# 3_3V-Regulator.net
KiCad netlist of a schematic drawn in Altium Designer
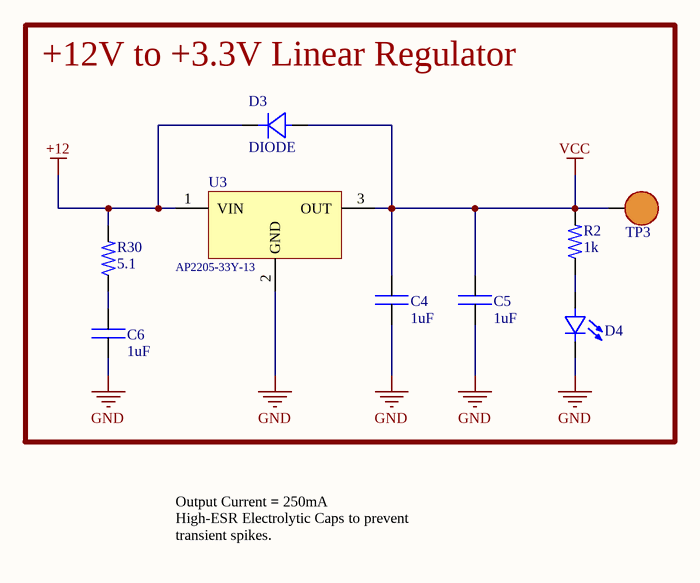
[diagram p0: 3.3V-Regulator.SchDoc]

(export (version "E")
  (design (tool "Eeschema 10.0.6"))
  (components
    (comp (ref "C4")
      (value "1uF")
      (footprint "Beethoven-clock:0402C")
      (description "Capacitor")
      (fields (field (name "MFR") "Murata Electronics") (field (name "Comment") "CAP"))
      (libsource (lib "Beethoven-clock") (part "CAP"))
    )
    (comp (ref "C5")
      (value "1uF")
      (footprint "Beethoven-clock:0402C")
      (description "Capacitor")
      (fields (field (name "MFR") "Murata Electronics") (field (name "Comment") "CAP"))
      (libsource (lib "Beethoven-clock") (part "CAP"))
    )
    (comp (ref "C6")
      (value "1uF")
      (footprint "Beethoven-clock:0402C")
      (description "Capacitor")
      (fields (field (name "MFR") "Murata Electronics") (field (name "Comment") "CAP"))
      (libsource (lib "Beethoven-clock") (part "CAP"))
    )
    (comp (ref "D3")
      (value "DIODE")
      (footprint "Beethoven-clock:DO-214AC")
      (description "DIODE GEN PURP")
      (fields (field (name "MFR") "Micro Commercial Co"))
      (libsource (lib "Beethoven-clock") (part "DIODE"))
    )
    (comp (ref "D4")
      (value "LED - single")
      (footprint "Beethoven-clock:LED - 0603")
      (description "LED")
      (fields (field (name "MFR") "DNS"))
      (libsource (lib "Beethoven-clock") (part "LED - single"))
    )
    (comp (ref "R2")
      (value "1k")
      (footprint "Beethoven-clock:0402R")
      (description "Resistor")
      (fields (field (name "MFR") "YAGEO") (field (name "Comment") "RES"))
      (libsource (lib "Beethoven-clock") (part "RES"))
    )
    (comp (ref "R30")
      (value "5.1")
      (footprint "Beethoven-clock:0805R")
      (description "Resistor")
      (fields (field (name "MFR") "Rohm Semiconductor") (field (name "Comment") "RES"))
      (libsource (lib "Beethoven-clock") (part "RES"))
    )
    (comp (ref "TP3")
      (value "RCWCTE")
      (footprint "Beethoven-clock:RCWCTE")
      (description "Test Point, Surface Mount")
      (fields (field (name "MFR") "KOA Speer Electronics, Inc."))
      (libsource (lib "Beethoven-clock") (part "TEST POINT"))
    )
    (comp (ref "U3")
      (value "AP2205-33Y-13")
      (footprint "Beethoven-clock:SOT-89-3")
      (description "IC REG LINEAR 3.3V 250MA SOT89-3")
      (fields (field (name "MFR") "Diodes Incorporated"))
      (libsource (lib "Beethoven-clock") (part "LIN REG 3.3V 250mA 24V"))
    )
  )
  (nets
    (net (code "1") (name "+12") (class "Default")
      (node (ref "D3") (pin "K") (pinfunction "K_K") (pintype "passive"))
      (node (ref "R30") (pin "2") (pinfunction "2_2") (pintype "passive"))
      (node (ref "U3") (pin "1") (pinfunction "VIN_1") (pintype "passive"))
    )
    (net (code "2") (name "GND") (class "Default")
      (node (ref "C4") (pin "1") (pinfunction "1_1") (pintype "passive"))
      (node (ref "C5") (pin "1") (pinfunction "1_1") (pintype "passive"))
      (node (ref "C6") (pin "1") (pinfunction "1_1") (pintype "passive"))
      (node (ref "D4") (pin "2") (pinfunction "C_2") (pintype "passive"))
      (node (ref "U3") (pin "2") (pinfunction "GND_2") (pintype "passive"))
    )
    (net (code "3") (name "Net-(C6-Pad2)") (class "Default")
      (node (ref "C6") (pin "2") (pinfunction "2_2") (pintype "passive"))
      (node (ref "R30") (pin "1") (pinfunction "1_1") (pintype "passive"))
    )
    (net (code "4") (name "Net-(D4-A)") (class "Default")
      (node (ref "D4") (pin "1") (pinfunction "A_1") (pintype "passive"))
      (node (ref "R2") (pin "1") (pinfunction "1_1") (pintype "passive"))
    )
    (net (code "5") (name "VCC") (class "Default")
      (node (ref "C4") (pin "2") (pinfunction "2_2") (pintype "passive"))
      (node (ref "C5") (pin "2") (pinfunction "2_2") (pintype "passive"))
      (node (ref "D3") (pin "A") (pinfunction "A_A") (pintype "passive"))
      (node (ref "R2") (pin "2") (pinfunction "2_2") (pintype "passive"))
      (node (ref "TP3") (pin "1") (pinfunction "0_1") (pintype "passive"))
      (node (ref "U3") (pin "3") (pinfunction "OUT_3") (pintype "passive"))
    )
  )
)
